# Led_orb.net
KiCad netlist of a schematic drawn in Altium Designer
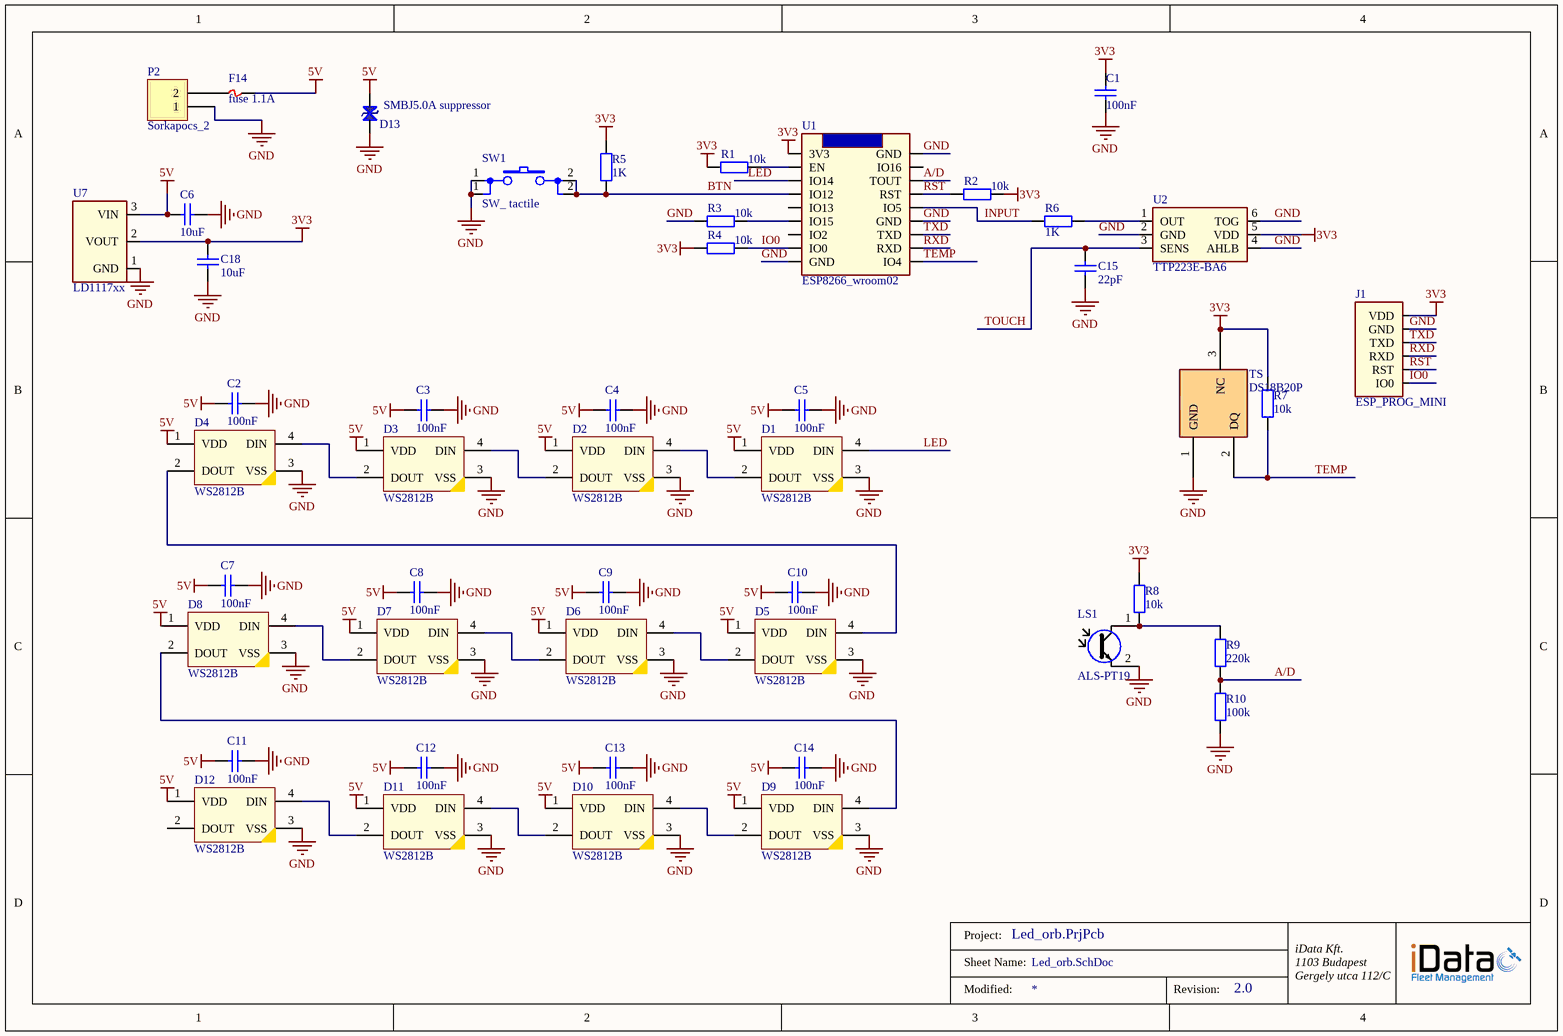
[diagram p0: Led_orb.SchDoc]

(export (version "E")
  (design (tool "Eeschema 10.0.6"))
  (components
    (comp (ref "C1")
      (value "100nF")
      (footprint "FP_0603_CAP_080")
      (description "Capacitor")
      (fields (field (name "PART NUMBER") "100nF_0603_50V_X7R_10percent"))
      (libsource (lib "Capacitor") (part "CAP"))
    )
    (comp (ref "C2")
      (value "100nF")
      (footprint "FP_0603_CAP_080")
      (description "Capacitor")
      (fields (field (name "PART NUMBER") "100nF_0603_50V_X7R_10percent"))
      (libsource (lib "Capacitor") (part "CAP"))
    )
    (comp (ref "C3")
      (value "100nF")
      (footprint "FP_0603_CAP_080")
      (description "Capacitor")
      (fields (field (name "PART NUMBER") "100nF_0603_50V_X7R_10percent"))
      (libsource (lib "Capacitor") (part "CAP"))
    )
    (comp (ref "C4")
      (value "100nF")
      (footprint "FP_0603_CAP_080")
      (description "Capacitor")
      (fields (field (name "PART NUMBER") "100nF_0603_50V_X7R_10percent"))
      (libsource (lib "Capacitor") (part "CAP"))
    )
    (comp (ref "C5")
      (value "100nF")
      (footprint "FP_0603_CAP_080")
      (description "Capacitor")
      (fields (field (name "PART NUMBER") "100nF_0603_50V_X7R_10percent"))
      (libsource (lib "Capacitor") (part "CAP"))
    )
    (comp (ref "C6")
      (value "10uF")
      (footprint "FP_1206_CAP_085")
      (description "Capacitor ceramic X7R")
      (libsource (lib "Capacitor") (part "Cap"))
    )
    (comp (ref "C7")
      (value "100nF")
      (footprint "FP_0603_CAP_080")
      (description "Capacitor")
      (fields (field (name "PART NUMBER") "100nF_0603_50V_X7R_10percent"))
      (libsource (lib "Capacitor") (part "CAP"))
    )
    (comp (ref "C8")
      (value "100nF")
      (footprint "FP_0603_CAP_080")
      (description "Capacitor")
      (fields (field (name "PART NUMBER") "100nF_0603_50V_X7R_10percent"))
      (libsource (lib "Capacitor") (part "CAP"))
    )
    (comp (ref "C9")
      (value "100nF")
      (footprint "FP_0603_CAP_080")
      (description "Capacitor")
      (fields (field (name "PART NUMBER") "100nF_0603_50V_X7R_10percent"))
      (libsource (lib "Capacitor") (part "CAP"))
    )
    (comp (ref "C10")
      (value "100nF")
      (footprint "FP_0603_CAP_080")
      (description "Capacitor")
      (fields (field (name "PART NUMBER") "100nF_0603_50V_X7R_10percent"))
      (libsource (lib "Capacitor") (part "CAP"))
    )
    (comp (ref "C11")
      (value "100nF")
      (footprint "FP_0603_CAP_080")
      (description "Capacitor")
      (fields (field (name "PART NUMBER") "100nF_0603_50V_X7R_10percent"))
      (libsource (lib "Capacitor") (part "CAP"))
    )
    (comp (ref "C12")
      (value "100nF")
      (footprint "FP_0603_CAP_080")
      (description "Capacitor")
      (fields (field (name "PART NUMBER") "100nF_0603_50V_X7R_10percent"))
      (libsource (lib "Capacitor") (part "CAP"))
    )
    (comp (ref "C13")
      (value "100nF")
      (footprint "FP_0603_CAP_080")
      (description "Capacitor")
      (fields (field (name "PART NUMBER") "100nF_0603_50V_X7R_10percent"))
      (libsource (lib "Capacitor") (part "CAP"))
    )
    (comp (ref "C14")
      (value "100nF")
      (footprint "FP_0603_CAP_080")
      (description "Capacitor")
      (fields (field (name "PART NUMBER") "100nF_0603_50V_X7R_10percent"))
      (libsource (lib "Capacitor") (part "CAP"))
    )
    (comp (ref "C15")
      (value "22pF")
      (footprint "FP_0603_CAP_080")
      (description "Capacitor")
      (fields (field (name "PART NUMBER") "22pF_0603_50V_NP0_5percent"))
      (libsource (lib "Miscellaneous Devices") (part "Cap"))
    )
    (comp (ref "C18")
      (value "10uF")
      (footprint "FP_1206_CAP_085")
      (description "Capacitor ceramic X7R")
      (libsource (lib "Capacitor") (part "Cap"))
    )
    (comp (ref "D1")
      (value "WS2812B")
      (footprint "LED_5050_4pin")
      (libsource (lib "Led_optical") (part "WS2812B"))
    )
    (comp (ref "D2")
      (value "WS2812B")
      (footprint "LED_5050_4pin")
      (libsource (lib "Led_optical") (part "WS2812B"))
    )
    (comp (ref "D3")
      (value "WS2812B")
      (footprint "LED_5050_4pin")
      (libsource (lib "Led_optical") (part "WS2812B"))
    )
    (comp (ref "D4")
      (value "WS2812B")
      (footprint "LED_5050_4pin")
      (libsource (lib "Led_optical") (part "WS2812B"))
    )
    (comp (ref "D5")
      (value "WS2812B")
      (footprint "LED_5050_4pin")
      (libsource (lib "Led_optical") (part "WS2812B"))
    )
    (comp (ref "D6")
      (value "WS2812B")
      (footprint "LED_5050_4pin")
      (libsource (lib "Led_optical") (part "WS2812B"))
    )
    (comp (ref "D7")
      (value "WS2812B")
      (footprint "LED_5050_4pin")
      (libsource (lib "Led_optical") (part "WS2812B"))
    )
    (comp (ref "D8")
      (value "WS2812B")
      (footprint "LED_5050_4pin")
      (libsource (lib "Led_optical") (part "WS2812B"))
    )
    (comp (ref "D9")
      (value "WS2812B")
      (footprint "LED_5050_4pin")
      (libsource (lib "Led_optical") (part "WS2812B"))
    )
    (comp (ref "D10")
      (value "WS2812B")
      (footprint "LED_5050_4pin")
      (libsource (lib "Led_optical") (part "WS2812B"))
    )
    (comp (ref "D11")
      (value "WS2812B")
      (footprint "LED_5050_4pin")
      (libsource (lib "Led_optical") (part "WS2812B"))
    )
    (comp (ref "D12")
      (value "WS2812B")
      (footprint "LED_5050_4pin")
      (libsource (lib "Led_optical") (part "WS2812B"))
    )
    (comp (ref "D13")
      (value "SMBJ5.0A suppressor")
      (footprint "FP_SMB DO214AA")
      (fields (field (name "PART NUMBER") "SMBJ5.0A"))
      (libsource (lib "Diode") (part "Suppressor diode"))
    )
    (comp (ref "F14")
      (value "fuse 1.1A")
      (footprint "Fuse-Littlefuse-1812")
      (description "fuse")
      (fields (field (name "PART NUMBER") "1812L110/33"))
      (libsource (lib "FUSE") (part "FUSE"))
    )
    (comp (ref "J1")
      (value "ESP_PROG_MINI")
      (footprint "ESP_PROG_MINI")
      (libsource (lib "Connector") (part "ESP_PROG_MINI"))
    )
    (comp (ref "LS1")
      (value "ALS-PT19")
      (footprint "ALS-PT19")
      (description "ALS-PT19 Ambient Light Sensor")
      (fields (field (name "PART NUMBER") "ALS-PT19-315C/L177/TR8"))
      (libsource (lib "Sensor") (part "ALS-PT19"))
    )
    (comp (ref "P2")
      (value "Sorkapocs_2")
      (footprint "Sorkapocs_5mm_2P")
      (description "Header, 2-Pin")
      (libsource (lib "Header") (part "Header 1X2"))
    )
    (comp (ref "R1")
      (value "10k")
      (footprint "FP_0603_RES")
      (description "Resistor")
      (fields (field (name "PART NUMBER") "10k_0603_1percent"))
      (libsource (lib "") (part "Res3_1"))
    )
    (comp (ref "R2")
      (value "10k")
      (footprint "FP_0603_RES")
      (description "Resistor")
      (fields (field (name "PART NUMBER") "10k_0603_1percent"))
      (libsource (lib "") (part "Res3_2"))
    )
    (comp (ref "R3")
      (value "10k")
      (footprint "FP_0603_RES")
      (description "Resistor")
      (fields (field (name "PART NUMBER") "10k_0603_1percent"))
      (libsource (lib "") (part "Res3_1"))
    )
    (comp (ref "R4")
      (value "10k")
      (footprint "FP_0603_RES")
      (description "Resistor")
      (fields (field (name "PART NUMBER") "10k_0603_1percent"))
      (libsource (lib "") (part "Res3_1"))
    )
    (comp (ref "R5")
      (value "1K")
      (footprint "FP_0603_RES")
      (description "Resistor")
      (fields (field (name "PART NUMBER") "1k_0603_1percent"))
      (libsource (lib "") (part "RES_1"))
    )
    (comp (ref "R6")
      (value "1K")
      (footprint "FP_0603_RES")
      (description "Resistor")
      (fields (field (name "PART NUMBER") "1k_0603_1percent"))
      (libsource (lib "Resistor") (part "RES"))
    )
    (comp (ref "R7")
      (value "10k")
      (footprint "FP_0603_RES")
      (description "Resistor")
      (fields (field (name "PART NUMBER") "10k_0603_1percent"))
      (libsource (lib "Miscellaneous Devices") (part "Res3"))
    )
    (comp (ref "R8")
      (value "10k")
      (footprint "FP_0603_RES")
      (description "Resistor")
      (fields (field (name "PART NUMBER") "10k_0603_1percent"))
      (libsource (lib "Miscellaneous Devices") (part "Res3"))
    )
    (comp (ref "R9")
      (value "220k")
      (footprint "FP_0603_RES")
      (description "Resistor")
      (fields (field (name "PART NUMBER") "220k_0603_1percent"))
      (libsource (lib "Miscellaneous Devices") (part "Res3"))
    )
    (comp (ref "R10")
      (value "100k")
      (footprint "FP_0603_RES")
      (description "Resistor")
      (fields (field (name "PART NUMBER") "100k_0603_1percent"))
      (libsource (lib "Miscellaneous Devices") (part "Res3"))
    )
    (comp (ref "SW1")
      (value "SW_ tactile")
      (footprint "FP_TACTBTN")
      (libsource (lib "Switch") (part "SW_ tactile"))
    )
    (comp (ref "TS")
      (value "DS18B20P")
      (footprint "SENSOR_TO92")
      (fields (field (name "PART NUMBER") "DS18B20+PAR"))
      (libsource (lib "Sensor") (part "DS18B20P"))
    )
    (comp (ref "U1")
      (value "ESP8266_wroom02")
      (footprint "ESP8266_wroom02")
      (description "ESP8266 WROOM 02 wifi module")
      (fields (field (name "PART NUMBER") "ESP_WROOM02"))
      (libsource (lib "Modul") (part "ESP8266_wroom02"))
    )
    (comp (ref "U2")
      (value "TTP223E-BA6")
      (footprint "SWITCH_SOT23-6")
      (description "SOT-23-6 Touch Sensor Controller ICs RoHS")
      (libsource (lib "Switch") (part "TTP223E-BA6"))
    )
    (comp (ref "U7")
      (value "LD1117xx")
      (footprint "SUPPLY_SOT223")
      (description "LD1117xx 3,3V lin reg")
      (libsource (lib "Supply") (part "LD1117xx"))
    )
  )
  (nets
    (net (code "1") (name "/A{slash}D") (class "Default")
      (node (ref "R10") (pin "2") (pinfunction "2_2") (pintype "passive"))
      (node (ref "R9") (pin "1") (pinfunction "1_1") (pintype "passive"))
      (node (ref "U1") (pin "16") (pinfunction "TOUT_16") (pintype "passive"))
    )
    (net (code "2") (name "/BTN") (class "Default")
      (node (ref "R5") (pin "2") (pinfunction "2_2") (pintype "passive"))
      (node (ref "SW1") (pin "2") (pinfunction "2_2") (pintype "passive"))
      (node (ref "U1") (pin "4") (pinfunction "IO12_4") (pintype "passive"))
    )
    (net (code "3") (name "/INPUT") (class "Default")
      (node (ref "R6") (pin "1") (pinfunction "1_1") (pintype "passive"))
      (node (ref "U1") (pin "14") (pinfunction "IO5_14") (pintype "passive"))
    )
    (net (code "4") (name "/IO0") (class "Default")
      (node (ref "J1") (pin "6") (pinfunction "IO0_6") (pintype "passive"))
      (node (ref "R4") (pin "1") (pinfunction "1_1") (pintype "passive"))
      (node (ref "U1") (pin "8") (pinfunction "IO0_8") (pintype "passive"))
    )
    (net (code "5") (name "/LED") (class "Default")
      (node (ref "D1") (pin "4") (pinfunction "DIN_4") (pintype "passive"))
      (node (ref "U1") (pin "3") (pinfunction "IO14_3") (pintype "passive"))
    )
    (net (code "6") (name "/RST") (class "Default")
      (node (ref "J1") (pin "5") (pinfunction "RST_5") (pintype "passive"))
      (node (ref "R2") (pin "1") (pinfunction "1_1") (pintype "passive"))
      (node (ref "U1") (pin "15") (pinfunction "RST_15") (pintype "passive"))
    )
    (net (code "7") (name "/RXD") (class "Default")
      (node (ref "J1") (pin "4") (pinfunction "RXD_4") (pintype "passive"))
      (node (ref "U1") (pin "11") (pinfunction "RXD_11") (pintype "passive"))
    )
    (net (code "8") (name "/TEMP") (class "Default")
      (node (ref "R7") (pin "1") (pinfunction "1_1") (pintype "passive"))
      (node (ref "TS") (pin "2") (pinfunction "DQ_2") (pintype "passive"))
      (node (ref "U1") (pin "10") (pinfunction "IO4_10") (pintype "passive"))
    )
    (net (code "9") (name "/TOUCH") (class "Default")
      (node (ref "C15") (pin "2") (pinfunction "2_2") (pintype "passive"))
      (node (ref "U2") (pin "3") (pinfunction "SENS_3") (pintype "passive"))
    )
    (net (code "10") (name "/TXD") (class "Default")
      (node (ref "J1") (pin "3") (pinfunction "TXD_3") (pintype "passive"))
      (node (ref "U1") (pin "12") (pinfunction "TXD_12") (pintype "passive"))
    )
    (net (code "11") (name "3V3") (class "Default")
      (node (ref "C1") (pin "2") (pinfunction "2_2") (pintype "passive"))
      (node (ref "C18") (pin "2") (pinfunction "2_2") (pintype "passive"))
      (node (ref "J1") (pin "1") (pinfunction "VDD_1") (pintype "passive"))
      (node (ref "R1") (pin "2") (pinfunction "2_2") (pintype "passive"))
      (node (ref "R2") (pin "2") (pinfunction "2_2") (pintype "passive"))
      (node (ref "R4") (pin "2") (pinfunction "2_2") (pintype "passive"))
      (node (ref "R5") (pin "1") (pinfunction "1_1") (pintype "passive"))
      (node (ref "R7") (pin "2") (pinfunction "2_2") (pintype "passive"))
      (node (ref "R8") (pin "2") (pinfunction "2_2") (pintype "passive"))
      (node (ref "TS") (pin "3") (pinfunction "NC_3") (pintype "passive"))
      (node (ref "U1") (pin "1") (pinfunction "3V3_1") (pintype "passive"))
      (node (ref "U2") (pin "5") (pinfunction "VDD_5") (pintype "passive"))
      (node (ref "U7") (pin "2") (pinfunction "VOUT_2") (pintype "passive"))
    )
    (net (code "12") (name "5V") (class "Default")
      (node (ref "C10") (pin "2") (pinfunction "2_2") (pintype "passive"))
      (node (ref "C11") (pin "2") (pinfunction "2_2") (pintype "passive"))
      (node (ref "C12") (pin "2") (pinfunction "2_2") (pintype "passive"))
      (node (ref "C13") (pin "2") (pinfunction "2_2") (pintype "passive"))
      (node (ref "C14") (pin "2") (pinfunction "2_2") (pintype "passive"))
      (node (ref "C2") (pin "2") (pinfunction "2_2") (pintype "passive"))
      (node (ref "C3") (pin "2") (pinfunction "2_2") (pintype "passive"))
      (node (ref "C4") (pin "2") (pinfunction "2_2") (pintype "passive"))
      (node (ref "C5") (pin "2") (pinfunction "2_2") (pintype "passive"))
      (node (ref "C6") (pin "2") (pinfunction "2_2") (pintype "passive"))
      (node (ref "C7") (pin "2") (pinfunction "2_2") (pintype "passive"))
      (node (ref "C8") (pin "2") (pinfunction "2_2") (pintype "passive"))
      (node (ref "C9") (pin "2") (pinfunction "2_2") (pintype "passive"))
      (node (ref "D1") (pin "1") (pinfunction "VDD_1") (pintype "passive"))
      (node (ref "D10") (pin "1") (pinfunction "VDD_1") (pintype "passive"))
      (node (ref "D11") (pin "1") (pinfunction "VDD_1") (pintype "passive"))
      (node (ref "D12") (pin "1") (pinfunction "VDD_1") (pintype "passive"))
      (node (ref "D13") (pin "K") (pinfunction "K_K") (pintype "passive"))
      (node (ref "D2") (pin "1") (pinfunction "VDD_1") (pintype "passive"))
      (node (ref "D3") (pin "1") (pinfunction "VDD_1") (pintype "passive"))
      (node (ref "D4") (pin "1") (pinfunction "VDD_1") (pintype "passive"))
      (node (ref "D5") (pin "1") (pinfunction "VDD_1") (pintype "passive"))
      (node (ref "D6") (pin "1") (pinfunction "VDD_1") (pintype "passive"))
      (node (ref "D7") (pin "1") (pinfunction "VDD_1") (pintype "passive"))
      (node (ref "D8") (pin "1") (pinfunction "VDD_1") (pintype "passive"))
      (node (ref "D9") (pin "1") (pinfunction "VDD_1") (pintype "passive"))
      (node (ref "F14") (pin "1") (pinfunction "1_1") (pintype "passive"))
      (node (ref "U7") (pin "3") (pinfunction "VIN_3") (pintype "passive"))
    )
    (net (code "13") (name "GND") (class "Default")
      (node (ref "C1") (pin "1") (pinfunction "1_1") (pintype "passive"))
      (node (ref "C10") (pin "1") (pinfunction "1_1") (pintype "passive"))
      (node (ref "C11") (pin "1") (pinfunction "1_1") (pintype "passive"))
      (node (ref "C12") (pin "1") (pinfunction "1_1") (pintype "passive"))
      (node (ref "C13") (pin "1") (pinfunction "1_1") (pintype "passive"))
      (node (ref "C14") (pin "1") (pinfunction "1_1") (pintype "passive"))
      (node (ref "C15") (pin "1") (pinfunction "1_1") (pintype "passive"))
      (node (ref "C18") (pin "1") (pinfunction "1_1") (pintype "passive"))
      (node (ref "C2") (pin "1") (pinfunction "1_1") (pintype "passive"))
      (node (ref "C3") (pin "1") (pinfunction "1_1") (pintype "passive"))
      (node (ref "C4") (pin "1") (pinfunction "1_1") (pintype "passive"))
      (node (ref "C5") (pin "1") (pinfunction "1_1") (pintype "passive"))
      (node (ref "C6") (pin "1") (pinfunction "1_1") (pintype "passive"))
      (node (ref "C7") (pin "1") (pinfunction "1_1") (pintype "passive"))
      (node (ref "C8") (pin "1") (pinfunction "1_1") (pintype "passive"))
      (node (ref "C9") (pin "1") (pinfunction "1_1") (pintype "passive"))
      (node (ref "D1") (pin "3") (pinfunction "VSS_3") (pintype "passive"))
      (node (ref "D10") (pin "3") (pinfunction "VSS_3") (pintype "passive"))
      (node (ref "D11") (pin "3") (pinfunction "VSS_3") (pintype "passive"))
      (node (ref "D12") (pin "3") (pinfunction "VSS_3") (pintype "passive"))
      (node (ref "D13") (pin "A") (pinfunction "A_A") (pintype "passive"))
      (node (ref "D2") (pin "3") (pinfunction "VSS_3") (pintype "passive"))
      (node (ref "D3") (pin "3") (pinfunction "VSS_3") (pintype "passive"))
      (node (ref "D4") (pin "3") (pinfunction "VSS_3") (pintype "passive"))
      (node (ref "D5") (pin "3") (pinfunction "VSS_3") (pintype "passive"))
      (node (ref "D6") (pin "3") (pinfunction "VSS_3") (pintype "passive"))
      (node (ref "D7") (pin "3") (pinfunction "VSS_3") (pintype "passive"))
      (node (ref "D8") (pin "3") (pinfunction "VSS_3") (pintype "passive"))
      (node (ref "D9") (pin "3") (pinfunction "VSS_3") (pintype "passive"))
      (node (ref "J1") (pin "2") (pinfunction "GND_2") (pintype "passive"))
      (node (ref "LS1") (pin "2") (pinfunction "2_2") (pintype "passive"))
      (node (ref "P2") (pin "1") (pinfunction "1_1") (pintype "passive"))
      (node (ref "R10") (pin "1") (pinfunction "1_1") (pintype "passive"))
      (node (ref "R3") (pin "2") (pinfunction "2_2") (pintype "passive"))
      (node (ref "SW1") (pin "1") (pinfunction "1_1") (pintype "passive"))
      (node (ref "TS") (pin "1") (pinfunction "GND_1") (pintype "passive"))
      (node (ref "U1") (pin "13") (pinfunction "GND_13") (pintype "passive"))
      (node (ref "U1") (pin "18") (pinfunction "GND_18") (pintype "passive"))
      (node (ref "U1") (pin "9") (pinfunction "GND_9") (pintype "passive"))
      (node (ref "U2") (pin "2") (pinfunction "GND_2") (pintype "passive"))
      (node (ref "U2") (pin "4") (pinfunction "AHLB_4") (pintype "passive"))
      (node (ref "U2") (pin "6") (pinfunction "TOG_6") (pintype "passive"))
      (node (ref "U7") (pin "1") (pinfunction "GND_1") (pintype "passive"))
    )
    (net (code "14") (name "Net-(D1-DOUT)") (class "Default")
      (node (ref "D1") (pin "2") (pinfunction "DOUT_2") (pintype "passive"))
      (node (ref "D2") (pin "4") (pinfunction "DIN_4") (pintype "passive"))
    )
    (net (code "15") (name "Net-(D2-DOUT)") (class "Default")
      (node (ref "D2") (pin "2") (pinfunction "DOUT_2") (pintype "passive"))
      (node (ref "D3") (pin "4") (pinfunction "DIN_4") (pintype "passive"))
    )
    (net (code "16") (name "Net-(D3-DOUT)") (class "Default")
      (node (ref "D3") (pin "2") (pinfunction "DOUT_2") (pintype "passive"))
      (node (ref "D4") (pin "4") (pinfunction "DIN_4") (pintype "passive"))
    )
    (net (code "17") (name "Net-(D4-DOUT)") (class "Default")
      (node (ref "D4") (pin "2") (pinfunction "DOUT_2") (pintype "passive"))
      (node (ref "D5") (pin "4") (pinfunction "DIN_4") (pintype "passive"))
    )
    (net (code "18") (name "Net-(D5-DOUT)") (class "Default")
      (node (ref "D5") (pin "2") (pinfunction "DOUT_2") (pintype "passive"))
      (node (ref "D6") (pin "4") (pinfunction "DIN_4") (pintype "passive"))
    )
    (net (code "19") (name "Net-(D6-DOUT)") (class "Default")
      (node (ref "D6") (pin "2") (pinfunction "DOUT_2") (pintype "passive"))
      (node (ref "D7") (pin "4") (pinfunction "DIN_4") (pintype "passive"))
    )
    (net (code "20") (name "Net-(D7-DOUT)") (class "Default")
      (node (ref "D7") (pin "2") (pinfunction "DOUT_2") (pintype "passive"))
      (node (ref "D8") (pin "4") (pinfunction "DIN_4") (pintype "passive"))
    )
    (net (code "21") (name "Net-(D8-DOUT)") (class "Default")
      (node (ref "D8") (pin "2") (pinfunction "DOUT_2") (pintype "passive"))
      (node (ref "D9") (pin "4") (pinfunction "DIN_4") (pintype "passive"))
    )
    (net (code "22") (name "Net-(D10-DIN)") (class "Default")
      (node (ref "D10") (pin "4") (pinfunction "DIN_4") (pintype "passive"))
      (node (ref "D9") (pin "2") (pinfunction "DOUT_2") (pintype "passive"))
    )
    (net (code "23") (name "Net-(D10-DOUT)") (class "Default")
      (node (ref "D10") (pin "2") (pinfunction "DOUT_2") (pintype "passive"))
      (node (ref "D11") (pin "4") (pinfunction "DIN_4") (pintype "passive"))
    )
    (net (code "24") (name "Net-(D11-DOUT)") (class "Default")
      (node (ref "D11") (pin "2") (pinfunction "DOUT_2") (pintype "passive"))
      (node (ref "D12") (pin "4") (pinfunction "DIN_4") (pintype "passive"))
    )
    (net (code "25") (name "Net-(F14-Pad2)") (class "Default")
      (node (ref "F14") (pin "2") (pinfunction "2_2") (pintype "passive"))
      (node (ref "P2") (pin "2") (pinfunction "2_2") (pintype "passive"))
    )
    (net (code "26") (name "Net-(LS1-Pad1)") (class "Default")
      (node (ref "LS1") (pin "1") (pinfunction "1_1") (pintype "passive"))
      (node (ref "R8") (pin "1") (pinfunction "1_1") (pintype "passive"))
      (node (ref "R9") (pin "2") (pinfunction "2_2") (pintype "passive"))
    )
    (net (code "27") (name "Net-(U1-EN)") (class "Default")
      (node (ref "R1") (pin "1") (pinfunction "1_1") (pintype "passive"))
      (node (ref "U1") (pin "2") (pinfunction "EN_2") (pintype "passive"))
    )
    (net (code "28") (name "Net-(U1-IO15)") (class "Default")
      (node (ref "R3") (pin "1") (pinfunction "1_1") (pintype "passive"))
      (node (ref "U1") (pin "6") (pinfunction "IO15_6") (pintype "passive"))
    )
    (net (code "29") (name "Net-(U2-OUT)") (class "Default")
      (node (ref "R6") (pin "2") (pinfunction "2_2") (pintype "passive"))
      (node (ref "U2") (pin "1") (pinfunction "OUT_1") (pintype "passive"))
    )
    (net (code "30") (name "unconnected-(D12-DOUT-Pad2)") (class "Default")
      (node (ref "D12") (pin "2") (pinfunction "DOUT_2") (pintype "passive"))
    )
    (net (code "31") (name "unconnected-(U1-IO2-Pad7)") (class "Default")
      (node (ref "U1") (pin "7") (pinfunction "IO2_7") (pintype "passive"))
    )
    (net (code "32") (name "unconnected-(U1-IO13-Pad5)") (class "Default")
      (node (ref "U1") (pin "5") (pinfunction "IO13_5") (pintype "passive"))
    )
    (net (code "33") (name "unconnected-(U1-IO16-Pad17)") (class "Default")
      (node (ref "U1") (pin "17") (pinfunction "IO16_17") (pintype "passive"))
    )
  )
)
